# LED.net
KiCad netlist of a schematic drawn in Altium Designer
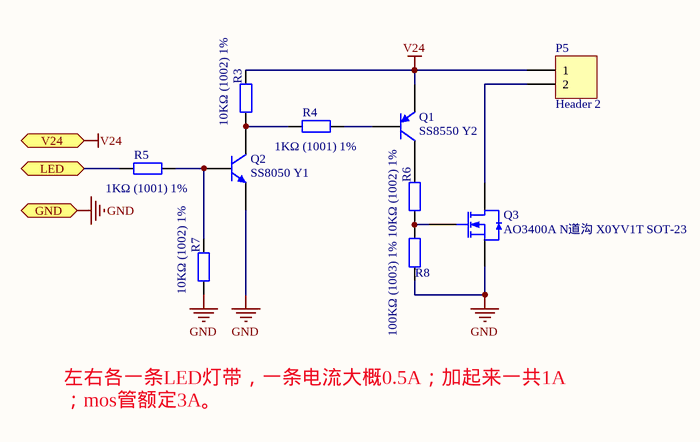
[diagram p0: LED.SchDoc]

(export (version "E")
  (design (tool "Eeschema 10.0.6"))
  (components
    (comp (ref "P5")
      (value "Header 2")
      (footprint "2P_XH2.54")
      (description "Header, 2-Pin")
      (fields (field (name "PUBLISHER") "Altium Limited"))
      (libsource (lib "Miscellaneous Connectors") (part "Header 2"))
    )
    (comp (ref "Q1")
      (value "SS8550 Y2")
      (footprint "SOT-23(SOT-23-3)")
      (description "三极管")
      (libsource (lib "Miscellaneous Devices LC") (part "SOT-23 SS8550 Y2"))
    )
    (comp (ref "Q2")
      (value "SS8050 Y1")
      (footprint "SOT-23(SOT-23-3)")
      (description "三极管")
      (libsource (lib "Miscellaneous Devices LC") (part "SOT-23 SS8050 Y1"))
    )
    (comp (ref "Q3")
      (value "AO3400A N道沟 X0YV1T SOT-23")
      (footprint "SOT-23-3L")
      (description "MOS(场效应管)")
      (libsource (lib "Miscellaneous Devices LC") (part "AO3400A N道沟 X0YV1T SOT-23"))
    )
    (comp (ref "R3")
      (value "10KΩ (1002) 1%")
      (footprint "0805_R")
      (description "贴片电阻")
      (libsource (lib "Miscellaneous Devices LC") (part "0805 10KΩ (1002) 1%"))
    )
    (comp (ref "R4")
      (value "1KΩ (1001) 1%")
      (footprint "0805_R")
      (description "贴片电阻")
      (libsource (lib "Miscellaneous Devices LC") (part "0805 1KΩ (1001) 1%"))
    )
    (comp (ref "R5")
      (value "1KΩ (1001) 1%")
      (footprint "0805_R")
      (description "贴片电阻")
      (libsource (lib "Miscellaneous Devices LC") (part "0805 1KΩ (1001) 1%"))
    )
    (comp (ref "R6")
      (value "10KΩ (1002) 1%")
      (footprint "0805_R")
      (description "贴片电阻")
      (libsource (lib "Miscellaneous Devices LC") (part "0805 10KΩ (1002) 1%"))
    )
    (comp (ref "R7")
      (value "10KΩ (1002) 1%")
      (footprint "0805_R")
      (description "贴片电阻")
      (libsource (lib "Miscellaneous Devices LC") (part "0805 10KΩ (1002) 1%"))
    )
    (comp (ref "R8")
      (value "100KΩ (1003) 1%")
      (footprint "0805_R")
      (description "贴片电阻")
      (libsource (lib "Miscellaneous Devices LC") (part "0805 100KΩ (1003) 1%"))
    )
  )
  (nets
    (net (code "1") (name "/LED") (class "Default")
      (node (ref "R5") (pin "2") (pinfunction "2_2") (pintype "passive"))
    )
    (net (code "2") (name "GND") (class "Default")
      (node (ref "Q2") (pin "2") (pinfunction "E_2") (pintype "passive"))
      (node (ref "Q3") (pin "2") (pinfunction "S_2") (pintype "passive"))
      (node (ref "R7") (pin "1") (pinfunction "1_1") (pintype "passive"))
      (node (ref "R8") (pin "2") (pinfunction "2_2") (pintype "passive"))
    )
    (net (code "3") (name "Net-(Q1-B)") (class "Default")
      (node (ref "Q1") (pin "1") (pinfunction "B_1") (pintype "passive"))
      (node (ref "R4") (pin "1") (pinfunction "1_1") (pintype "passive"))
    )
    (net (code "4") (name "Net-(Q1-C)") (class "Default")
      (node (ref "Q1") (pin "3") (pinfunction "C_3") (pintype "passive"))
      (node (ref "R6") (pin "2") (pinfunction "2_2") (pintype "passive"))
    )
    (net (code "5") (name "Net-(Q2-B)") (class "Default")
      (node (ref "Q2") (pin "1") (pinfunction "B_1") (pintype "passive"))
      (node (ref "R5") (pin "1") (pinfunction "1_1") (pintype "passive"))
      (node (ref "R7") (pin "2") (pinfunction "2_2") (pintype "passive"))
    )
    (net (code "6") (name "Net-(Q2-C)") (class "Default")
      (node (ref "Q2") (pin "3") (pinfunction "C_3") (pintype "passive"))
      (node (ref "R3") (pin "1") (pinfunction "1_1") (pintype "passive"))
      (node (ref "R4") (pin "2") (pinfunction "2_2") (pintype "passive"))
    )
    (net (code "7") (name "Net-(Q3-D)") (class "Default")
      (node (ref "P5") (pin "2") (pinfunction "2_2") (pintype "passive"))
      (node (ref "Q3") (pin "3") (pinfunction "D_3") (pintype "passive"))
    )
    (net (code "8") (name "Net-(Q3-G)") (class "Default")
      (node (ref "Q3") (pin "1") (pinfunction "G_1") (pintype "passive"))
      (node (ref "R6") (pin "1") (pinfunction "1_1") (pintype "passive"))
      (node (ref "R8") (pin "1") (pinfunction "1_1") (pintype "passive"))
    )
    (net (code "9") (name "V24") (class "Default")
      (node (ref "P5") (pin "1") (pinfunction "1_1") (pintype "passive"))
      (node (ref "Q1") (pin "2") (pinfunction "E_2") (pintype "passive"))
      (node (ref "R3") (pin "2") (pinfunction "2_2") (pintype "passive"))
    )
  )
)
